# MCU.net
KiCad netlist of a schematic drawn in Altium Designer
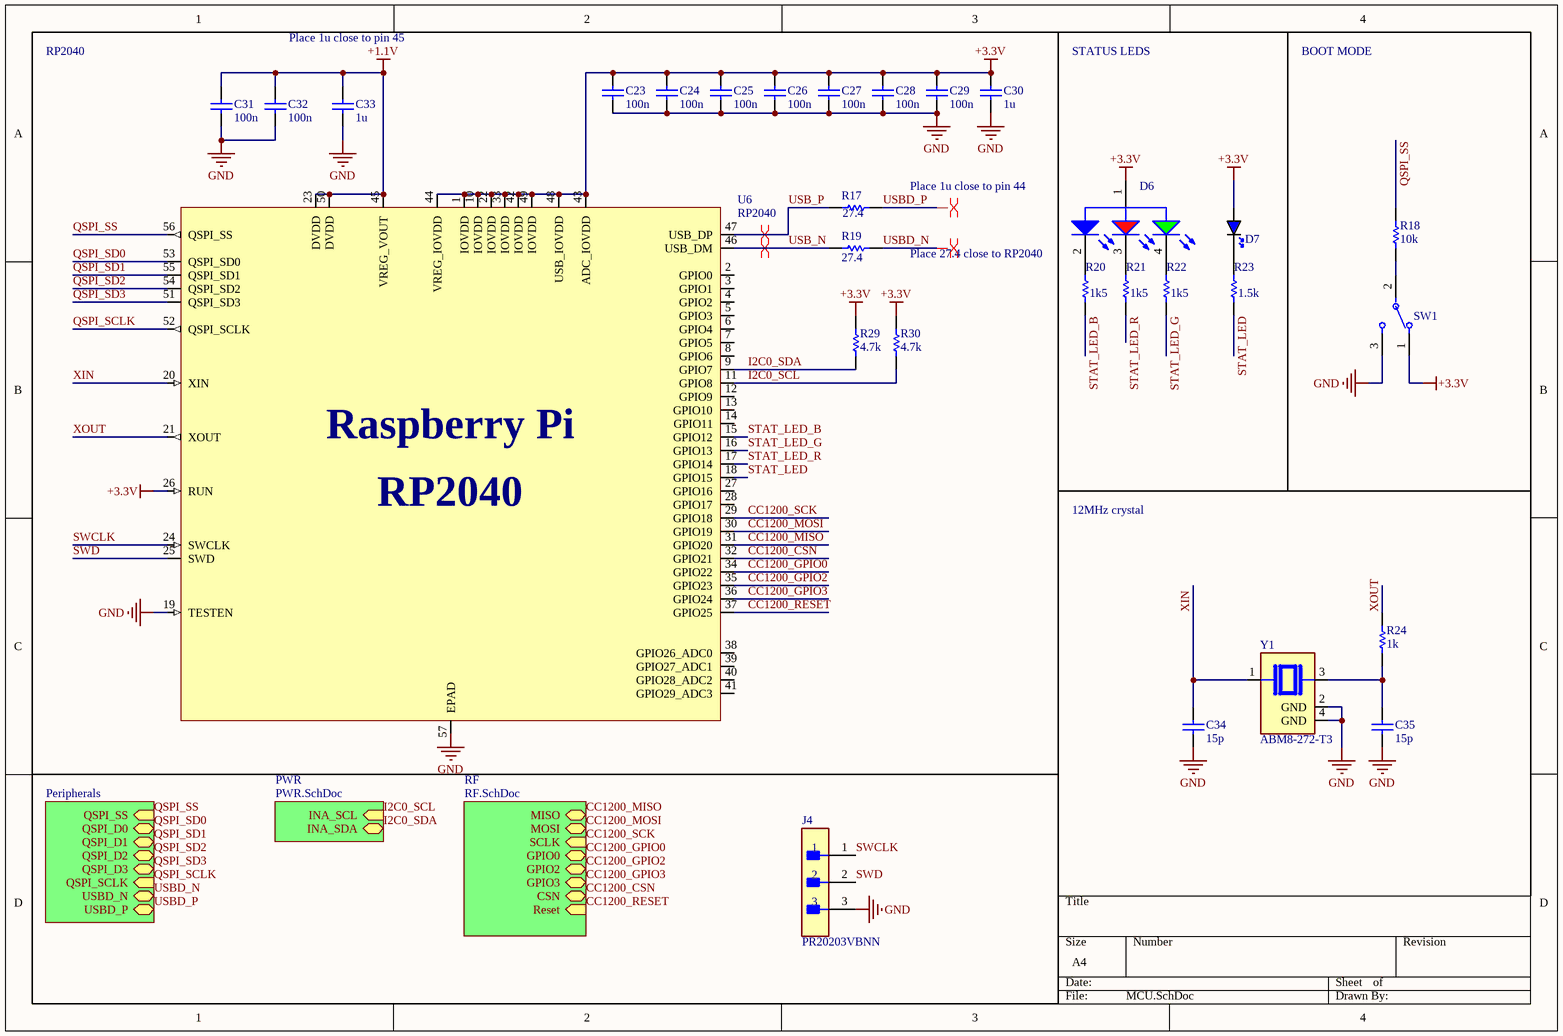
[diagram p0: MCU.SchDoc]

(export (version "E")
  (design (tool "Eeschema 10.0.6"))
  (components
    (comp (ref "C23")
      (value "100n")
      (footprint "RES_0805")
      (description "Capacitor")
      (libsource (lib "Simulation Generic Components") (part "Capacitor"))
    )
    (comp (ref "C24")
      (value "100n")
      (footprint "RES_0805")
      (description "Capacitor")
      (libsource (lib "Simulation Generic Components") (part "Capacitor"))
    )
    (comp (ref "C25")
      (value "100n")
      (footprint "RES_0805")
      (description "Capacitor")
      (libsource (lib "Simulation Generic Components") (part "Capacitor"))
    )
    (comp (ref "C26")
      (value "100n")
      (footprint "RES_0805")
      (description "Capacitor")
      (libsource (lib "Simulation Generic Components") (part "Capacitor"))
    )
    (comp (ref "C27")
      (value "100n")
      (footprint "RES_0805")
      (description "Capacitor")
      (libsource (lib "Simulation Generic Components") (part "Capacitor"))
    )
    (comp (ref "C28")
      (value "100n")
      (footprint "RES_0805")
      (description "Capacitor")
      (libsource (lib "Simulation Generic Components") (part "Capacitor"))
    )
    (comp (ref "C29")
      (value "100n")
      (footprint "RES_0805")
      (description "Capacitor")
      (libsource (lib "Simulation Generic Components") (part "Capacitor"))
    )
    (comp (ref "C30")
      (value "1u")
      (footprint "RES_0805")
      (description "Capacitor")
      (libsource (lib "Simulation Generic Components") (part "Capacitor"))
    )
    (comp (ref "C31")
      (value "100n")
      (footprint "RES_0805")
      (description "Capacitor")
      (libsource (lib "Simulation Generic Components") (part "Capacitor"))
    )
    (comp (ref "C32")
      (value "100n")
      (footprint "RES_0805")
      (description "Capacitor")
      (libsource (lib "Simulation Generic Components") (part "Capacitor"))
    )
    (comp (ref "C33")
      (value "1u")
      (footprint "RES_0805")
      (description "Capacitor")
      (libsource (lib "Simulation Generic Components") (part "Capacitor"))
    )
    (comp (ref "C34")
      (value "15p")
      (footprint "RES_0805")
      (description "Capacitor")
      (libsource (lib "Simulation Generic Components") (part "Capacitor"))
    )
    (comp (ref "C35")
      (value "15p")
      (footprint "RES_0805")
      (description "Capacitor")
      (libsource (lib "Simulation Generic Components") (part "Capacitor"))
    )
    (comp (ref "D6")
      (value "150141M173100")
      (footprint "WL-SFTW_3528_150141M173100")
      (libsource (lib "Altium Content Vault") (part "WL-SFTW_150141M173100"))
    )
    (comp (ref "D7")
      (value "BLUE")
      (footprint "LED_0805_BLUE")
      (description "LED 0805 BLUE SMD")
      (libsource (lib "Schematic-Lib-PhilsLab") (part "LED_0805_BLUE"))
    )
    (comp (ref "J4")
      (value "PR20203VBNN")
      (footprint "FP-PR20203VBNN-MFG")
      (description "CONN HEADER VERT 3POS 2.54MM")
      (fields
        (field (name "OCTOPART") "https://octopart.com/pr20203vbnn-metz+connect-87667116")
        (field (name "MANUFACTURER") "Metz Connect")
      )
      (libsource (lib "Altium Content Vault") (part "0d3f023dd272f625e17a2be33dea85f"))
    )
    (comp (ref "R17")
      (value "27.4")
      (footprint "RES_0805")
      (description "Resistor")
      (libsource (lib "Simulation Generic Components") (part "Resistor"))
    )
    (comp (ref "R18")
      (value "10k")
      (footprint "RES_0603")
      (description "Resistor")
      (libsource (lib "Simulation Generic Components") (part "Resistor"))
    )
    (comp (ref "R19")
      (value "27.4")
      (footprint "RES_0805")
      (description "Resistor")
      (libsource (lib "Simulation Generic Components") (part "Resistor"))
    )
    (comp (ref "R20")
      (value "1k5")
      (footprint "RES_0805")
      (description "Resistor")
      (libsource (lib "Simulation Generic Components") (part "Resistor"))
    )
    (comp (ref "R21")
      (value "1k5")
      (footprint "RES_0805")
      (description "Resistor")
      (libsource (lib "Simulation Generic Components") (part "Resistor"))
    )
    (comp (ref "R22")
      (value "1k5")
      (footprint "RES_0805")
      (description "Resistor")
      (libsource (lib "Simulation Generic Components") (part "Resistor"))
    )
    (comp (ref "R23")
      (value "1.5k")
      (footprint "RES_0805")
      (description "Resistor")
      (libsource (lib "Simulation Generic Components") (part "Resistor"))
    )
    (comp (ref "R24")
      (value "1k")
      (footprint "RES_0805")
      (description "Resistor")
      (libsource (lib "Simulation Generic Components") (part "Resistor"))
    )
    (comp (ref "R29")
      (value "4.7k")
      (footprint "RES_0805")
      (description "Resistor")
      (libsource (lib "Simulation Generic Components") (part "Resistor"))
    )
    (comp (ref "R30")
      (value "4.7k")
      (footprint "RES_0805")
      (description "Resistor")
      (libsource (lib "Simulation Generic Components") (part "Resistor"))
    )
    (comp (ref "SW1")
      (value "JS102011SAQN")
      (footprint "FP-JS102011SAQN-MFG")
      (description "SWITCH SLIDE SPDT 300MA 6V")
      (libsource (lib "Altium Content Vault") (part "39e195cbbadc85d1df0d7eb6847d379"))
    )
    (comp (ref "U6")
      (value "RP2040")
      (footprint "QFN-56-EP")
      (description "32-Bit Dual-Core ARM Cortex-M0+ Microcontroller")
      (fields (field (name "MANUFACTURER") "Raspberry Pi"))
      (libsource (lib "Schematic-Lib-PhilsLab") (part "RP2040"))
    )
    (comp (ref "Y1")
      (value "ABM8-272-T3")
      (footprint "XTAL_ABM8-272-T3")
      (description "12 MHz Â±30ppm Crystal 10pF 50 Ohms 4-SMD, No Lead")
      (fields (field (name "MF") "ABRACON"))
      (libsource (lib "ABM8-272-T3") (part "ABM8-272-T3"))
    )
  )
  (nets
    (net (code "1") (name "+1.1V") (class "Default")
      (node (ref "C31") (pin "1") (pinfunction "1_1") (pintype "passive"))
      (node (ref "C32") (pin "1") (pinfunction "1_1") (pintype "passive"))
      (node (ref "C33") (pin "1") (pinfunction "1_1") (pintype "passive"))
      (node (ref "U6") (pin "23") (pinfunction "DVDD_23") (pintype "power_in"))
      (node (ref "U6") (pin "45") (pinfunction "VREG_VOUT_45") (pintype "power_in"))
      (node (ref "U6") (pin "50") (pinfunction "DVDD_50") (pintype "power_in"))
    )
    (net (code "2") (name "+3.3V") (class "Default")
      (node (ref "C23") (pin "1") (pinfunction "1_1") (pintype "passive"))
      (node (ref "C24") (pin "1") (pinfunction "1_1") (pintype "passive"))
      (node (ref "C25") (pin "1") (pinfunction "1_1") (pintype "passive"))
      (node (ref "C26") (pin "1") (pinfunction "1_1") (pintype "passive"))
      (node (ref "C27") (pin "1") (pinfunction "1_1") (pintype "passive"))
      (node (ref "C28") (pin "1") (pinfunction "1_1") (pintype "passive"))
      (node (ref "C29") (pin "1") (pinfunction "1_1") (pintype "passive"))
      (node (ref "C30") (pin "1") (pinfunction "1_1") (pintype "passive"))
      (node (ref "D6") (pin "1") (pinfunction "A_1") (pintype "passive"))
      (node (ref "D7") (pin "A") (pinfunction "A_A") (pintype "passive"))
      (node (ref "R29") (pin "2") (pinfunction "2_2") (pintype "passive"))
      (node (ref "R30") (pin "2") (pinfunction "2_2") (pintype "passive"))
      (node (ref "SW1") (pin "1") (pinfunction "1_1") (pintype "passive"))
      (node (ref "U6") (pin "1") (pinfunction "IOVDD_1") (pintype "power_in"))
      (node (ref "U6") (pin "10") (pinfunction "IOVDD_10") (pintype "power_in"))
      (node (ref "U6") (pin "22") (pinfunction "IOVDD_22") (pintype "power_in"))
      (node (ref "U6") (pin "26") (pinfunction "RUN_26") (pintype "input"))
      (node (ref "U6") (pin "33") (pinfunction "IOVDD_33") (pintype "power_in"))
      (node (ref "U6") (pin "42") (pinfunction "IOVDD_42") (pintype "power_in"))
      (node (ref "U6") (pin "43") (pinfunction "ADC_IOVDD_43") (pintype "power_in"))
      (node (ref "U6") (pin "44") (pinfunction "VREG_IOVDD_44") (pintype "power_in"))
      (node (ref "U6") (pin "48") (pinfunction "USB_IOVDD_48") (pintype "power_in"))
      (node (ref "U6") (pin "49") (pinfunction "IOVDD_49") (pintype "power_in"))
    )
    (net (code "3") (name "/CC1200_CSN") (class "Default")
      (node (ref "U6") (pin "32") (pinfunction "GPIO21_32") (pintype "bidirectional"))
    )
    (net (code "4") (name "/CC1200_GPIO0") (class "Default")
      (node (ref "U6") (pin "34") (pinfunction "GPIO22_34") (pintype "bidirectional"))
    )
    (net (code "5") (name "/CC1200_GPIO2") (class "Default")
      (node (ref "U6") (pin "35") (pinfunction "GPIO23_35") (pintype "bidirectional"))
    )
    (net (code "6") (name "/CC1200_GPIO3") (class "Default")
      (node (ref "U6") (pin "36") (pinfunction "GPIO24_36") (pintype "bidirectional"))
    )
    (net (code "7") (name "/CC1200_MISO") (class "Default")
      (node (ref "U6") (pin "31") (pinfunction "GPIO20_31") (pintype "bidirectional"))
    )
    (net (code "8") (name "/CC1200_MOSI") (class "Default")
      (node (ref "U6") (pin "30") (pinfunction "GPIO19_30") (pintype "bidirectional"))
    )
    (net (code "9") (name "/CC1200_RESET") (class "Default")
      (node (ref "U6") (pin "37") (pinfunction "GPIO25_37") (pintype "bidirectional"))
    )
    (net (code "10") (name "/CC1200_SCK") (class "Default")
      (node (ref "U6") (pin "29") (pinfunction "GPIO18_29") (pintype "bidirectional"))
    )
    (net (code "11") (name "/I2C0_SCL") (class "Default")
      (node (ref "R30") (pin "1") (pinfunction "1_1") (pintype "passive"))
      (node (ref "U6") (pin "11") (pinfunction "GPIO8_11") (pintype "bidirectional"))
    )
    (net (code "12") (name "/I2C0_SDA") (class "Default")
      (node (ref "R29") (pin "1") (pinfunction "1_1") (pintype "passive"))
      (node (ref "U6") (pin "9") (pinfunction "GPIO7_9") (pintype "bidirectional"))
    )
    (net (code "13") (name "/QSPI_SCLK") (class "Default")
      (node (ref "U6") (pin "52") (pinfunction "QSPI_SCLK_52") (pintype "output"))
    )
    (net (code "14") (name "/QSPI_SD0") (class "Default")
      (node (ref "U6") (pin "53") (pinfunction "QSPI_SD0_53") (pintype "bidirectional"))
    )
    (net (code "15") (name "/QSPI_SD1") (class "Default")
      (node (ref "U6") (pin "55") (pinfunction "QSPI_SD1_55") (pintype "bidirectional"))
    )
    (net (code "16") (name "/QSPI_SD2") (class "Default")
      (node (ref "U6") (pin "54") (pinfunction "QSPI_SD2_54") (pintype "bidirectional"))
    )
    (net (code "17") (name "/QSPI_SD3") (class "Default")
      (node (ref "U6") (pin "51") (pinfunction "QSPI_SD3_51") (pintype "bidirectional"))
    )
    (net (code "18") (name "/QSPI_SS") (class "Default")
      (node (ref "R18") (pin "1") (pinfunction "1_1") (pintype "passive"))
      (node (ref "U6") (pin "56") (pinfunction "QSPI_SS_56") (pintype "output"))
    )
    (net (code "19") (name "/STAT_LED") (class "Default")
      (node (ref "R23") (pin "2") (pinfunction "2_2") (pintype "passive"))
      (node (ref "U6") (pin "18") (pinfunction "GPIO15_18") (pintype "bidirectional"))
    )
    (net (code "20") (name "/STAT_LED_B") (class "Default")
      (node (ref "R20") (pin "2") (pinfunction "2_2") (pintype "passive"))
      (node (ref "U6") (pin "15") (pinfunction "GPIO12_15") (pintype "bidirectional"))
    )
    (net (code "21") (name "/STAT_LED_G") (class "Default")
      (node (ref "R22") (pin "2") (pinfunction "2_2") (pintype "passive"))
      (node (ref "U6") (pin "16") (pinfunction "GPIO13_16") (pintype "bidirectional"))
    )
    (net (code "22") (name "/STAT_LED_R") (class "Default")
      (node (ref "R21") (pin "2") (pinfunction "2_2") (pintype "passive"))
      (node (ref "U6") (pin "17") (pinfunction "GPIO14_17") (pintype "bidirectional"))
    )
    (net (code "23") (name "/SWCLK") (class "Default")
      (node (ref "J4") (pin "1") (pinfunction "1_1") (pintype "passive"))
      (node (ref "U6") (pin "24") (pinfunction "SWCLK_24") (pintype "input"))
    )
    (net (code "24") (name "/SWD") (class "Default")
      (node (ref "J4") (pin "2") (pinfunction "2_2") (pintype "passive"))
      (node (ref "U6") (pin "25") (pinfunction "SWD_25") (pintype "bidirectional"))
    )
    (net (code "25") (name "/USBD_N") (class "Default")
      (node (ref "R19") (pin "2") (pinfunction "2_2") (pintype "passive"))
    )
    (net (code "26") (name "/USBD_P") (class "Default")
      (node (ref "R17") (pin "2") (pinfunction "2_2") (pintype "passive"))
    )
    (net (code "27") (name "/USB_N") (class "Default")
      (node (ref "R19") (pin "1") (pinfunction "1_1") (pintype "passive"))
      (node (ref "U6") (pin "46") (pinfunction "USB_DM_46") (pintype "bidirectional"))
    )
    (net (code "28") (name "/USB_P") (class "Default")
      (node (ref "R17") (pin "1") (pinfunction "1_1") (pintype "passive"))
      (node (ref "U6") (pin "47") (pinfunction "USB_DP_47") (pintype "bidirectional"))
    )
    (net (code "29") (name "/XIN") (class "Default")
      (node (ref "C34") (pin "1") (pinfunction "1_1") (pintype "passive"))
      (node (ref "U6") (pin "20") (pinfunction "XIN_20") (pintype "input"))
      (node (ref "Y1") (pin "1") (pinfunction "1_1") (pintype "passive"))
    )
    (net (code "30") (name "/XOUT") (class "Default")
      (node (ref "R24") (pin "2") (pinfunction "2_2") (pintype "passive"))
      (node (ref "U6") (pin "21") (pinfunction "XOUT_21") (pintype "output"))
    )
    (net (code "31") (name "GND") (class "Default")
      (node (ref "C23") (pin "2") (pinfunction "2_2") (pintype "passive"))
      (node (ref "C24") (pin "2") (pinfunction "2_2") (pintype "passive"))
      (node (ref "C25") (pin "2") (pinfunction "2_2") (pintype "passive"))
      (node (ref "C26") (pin "2") (pinfunction "2_2") (pintype "passive"))
      (node (ref "C27") (pin "2") (pinfunction "2_2") (pintype "passive"))
      (node (ref "C28") (pin "2") (pinfunction "2_2") (pintype "passive"))
      (node (ref "C29") (pin "2") (pinfunction "2_2") (pintype "passive"))
      (node (ref "C30") (pin "2") (pinfunction "2_2") (pintype "passive"))
      (node (ref "C31") (pin "2") (pinfunction "2_2") (pintype "passive"))
      (node (ref "C32") (pin "2") (pinfunction "2_2") (pintype "passive"))
      (node (ref "C33") (pin "2") (pinfunction "2_2") (pintype "passive"))
      (node (ref "C34") (pin "2") (pinfunction "2_2") (pintype "passive"))
      (node (ref "C35") (pin "2") (pinfunction "2_2") (pintype "passive"))
      (node (ref "J4") (pin "3") (pinfunction "3_3") (pintype "passive"))
      (node (ref "SW1") (pin "3") (pinfunction "3_3") (pintype "passive"))
      (node (ref "U6") (pin "19") (pinfunction "TESTEN_19") (pintype "input"))
      (node (ref "U6") (pin "57") (pinfunction "EPAD_57") (pintype "power_in"))
      (node (ref "Y1") (pin "2") (pinfunction "GND_2") (pintype "power_in"))
      (node (ref "Y1") (pin "4") (pinfunction "GND_4") (pintype "power_in"))
    )
    (net (code "32") (name "Net-(C35-Pad1)") (class "Default")
      (node (ref "C35") (pin "1") (pinfunction "1_1") (pintype "passive"))
      (node (ref "R24") (pin "1") (pinfunction "1_1") (pintype "passive"))
      (node (ref "Y1") (pin "3") (pinfunction "3_3") (pintype "passive"))
    )
    (net (code "33") (name "Net-(D6-K-Pad2)") (class "Default")
      (node (ref "D6") (pin "2") (pinfunction "K_2") (pintype "passive"))
      (node (ref "R20") (pin "1") (pinfunction "1_1") (pintype "passive"))
    )
    (net (code "34") (name "Net-(D6-K-Pad3)") (class "Default")
      (node (ref "D6") (pin "3") (pinfunction "K_3") (pintype "passive"))
      (node (ref "R21") (pin "1") (pinfunction "1_1") (pintype "passive"))
    )
    (net (code "35") (name "Net-(D6-K-Pad4)") (class "Default")
      (node (ref "D6") (pin "4") (pinfunction "K_4") (pintype "passive"))
      (node (ref "R22") (pin "1") (pinfunction "1_1") (pintype "passive"))
    )
    (net (code "36") (name "Net-(D7-PadK)") (class "Default")
      (node (ref "D7") (pin "K") (pinfunction "K_K") (pintype "passive"))
      (node (ref "R23") (pin "1") (pinfunction "1_1") (pintype "passive"))
    )
    (net (code "37") (name "Net-(SW1-C)") (class "Default")
      (node (ref "R18") (pin "2") (pinfunction "2_2") (pintype "passive"))
      (node (ref "SW1") (pin "2") (pinfunction "C_2") (pintype "passive"))
    )
    (net (code "38") (name "unconnected-(U6-GPIO0-Pad2)") (class "Default")
      (node (ref "U6") (pin "2") (pinfunction "GPIO0_2") (pintype "bidirectional"))
    )
    (net (code "39") (name "unconnected-(U6-GPIO1-Pad3)") (class "Default")
      (node (ref "U6") (pin "3") (pinfunction "GPIO1_3") (pintype "bidirectional"))
    )
    (net (code "40") (name "unconnected-(U6-GPIO2-Pad4)") (class "Default")
      (node (ref "U6") (pin "4") (pinfunction "GPIO2_4") (pintype "bidirectional"))
    )
    (net (code "41") (name "unconnected-(U6-GPIO3-Pad5)") (class "Default")
      (node (ref "U6") (pin "5") (pinfunction "GPIO3_5") (pintype "bidirectional"))
    )
    (net (code "42") (name "unconnected-(U6-GPIO4-Pad6)") (class "Default")
      (node (ref "U6") (pin "6") (pinfunction "GPIO4_6") (pintype "bidirectional"))
    )
    (net (code "43") (name "unconnected-(U6-GPIO5-Pad7)") (class "Default")
      (node (ref "U6") (pin "7") (pinfunction "GPIO5_7") (pintype "bidirectional"))
    )
    (net (code "44") (name "unconnected-(U6-GPIO6-Pad8)") (class "Default")
      (node (ref "U6") (pin "8") (pinfunction "GPIO6_8") (pintype "bidirectional"))
    )
    (net (code "45") (name "unconnected-(U6-GPIO9-Pad12)") (class "Default")
      (node (ref "U6") (pin "12") (pinfunction "GPIO9_12") (pintype "bidirectional"))
    )
    (net (code "46") (name "unconnected-(U6-GPIO10-Pad13)") (class "Default")
      (node (ref "U6") (pin "13") (pinfunction "GPIO10_13") (pintype "bidirectional"))
    )
    (net (code "47") (name "unconnected-(U6-GPIO11-Pad14)") (class "Default")
      (node (ref "U6") (pin "14") (pinfunction "GPIO11_14") (pintype "bidirectional"))
    )
    (net (code "48") (name "unconnected-(U6-GPIO16-Pad27)") (class "Default")
      (node (ref "U6") (pin "27") (pinfunction "GPIO16_27") (pintype "bidirectional"))
    )
    (net (code "49") (name "unconnected-(U6-GPIO17-Pad28)") (class "Default")
      (node (ref "U6") (pin "28") (pinfunction "GPIO17_28") (pintype "bidirectional"))
    )
    (net (code "50") (name "unconnected-(U6-GPIO26_ADC0-Pad38)") (class "Default")
      (node (ref "U6") (pin "38") (pinfunction "GPIO26_ADC0_38") (pintype "bidirectional"))
    )
    (net (code "51") (name "unconnected-(U6-GPIO27_ADC1-Pad39)") (class "Default")
      (node (ref "U6") (pin "39") (pinfunction "GPIO27_ADC1_39") (pintype "bidirectional"))
    )
    (net (code "52") (name "unconnected-(U6-GPIO28_ADC2-Pad40)") (class "Default")
      (node (ref "U6") (pin "40") (pinfunction "GPIO28_ADC2_40") (pintype "bidirectional"))
    )
    (net (code "53") (name "unconnected-(U6-GPIO29_ADC3-Pad41)") (class "Default")
      (node (ref "U6") (pin "41") (pinfunction "GPIO29_ADC3_41") (pintype "bidirectional"))
    )
  )
)
